# p1_control_block.net
KiCad netlist of a schematic drawn in Altium Designer
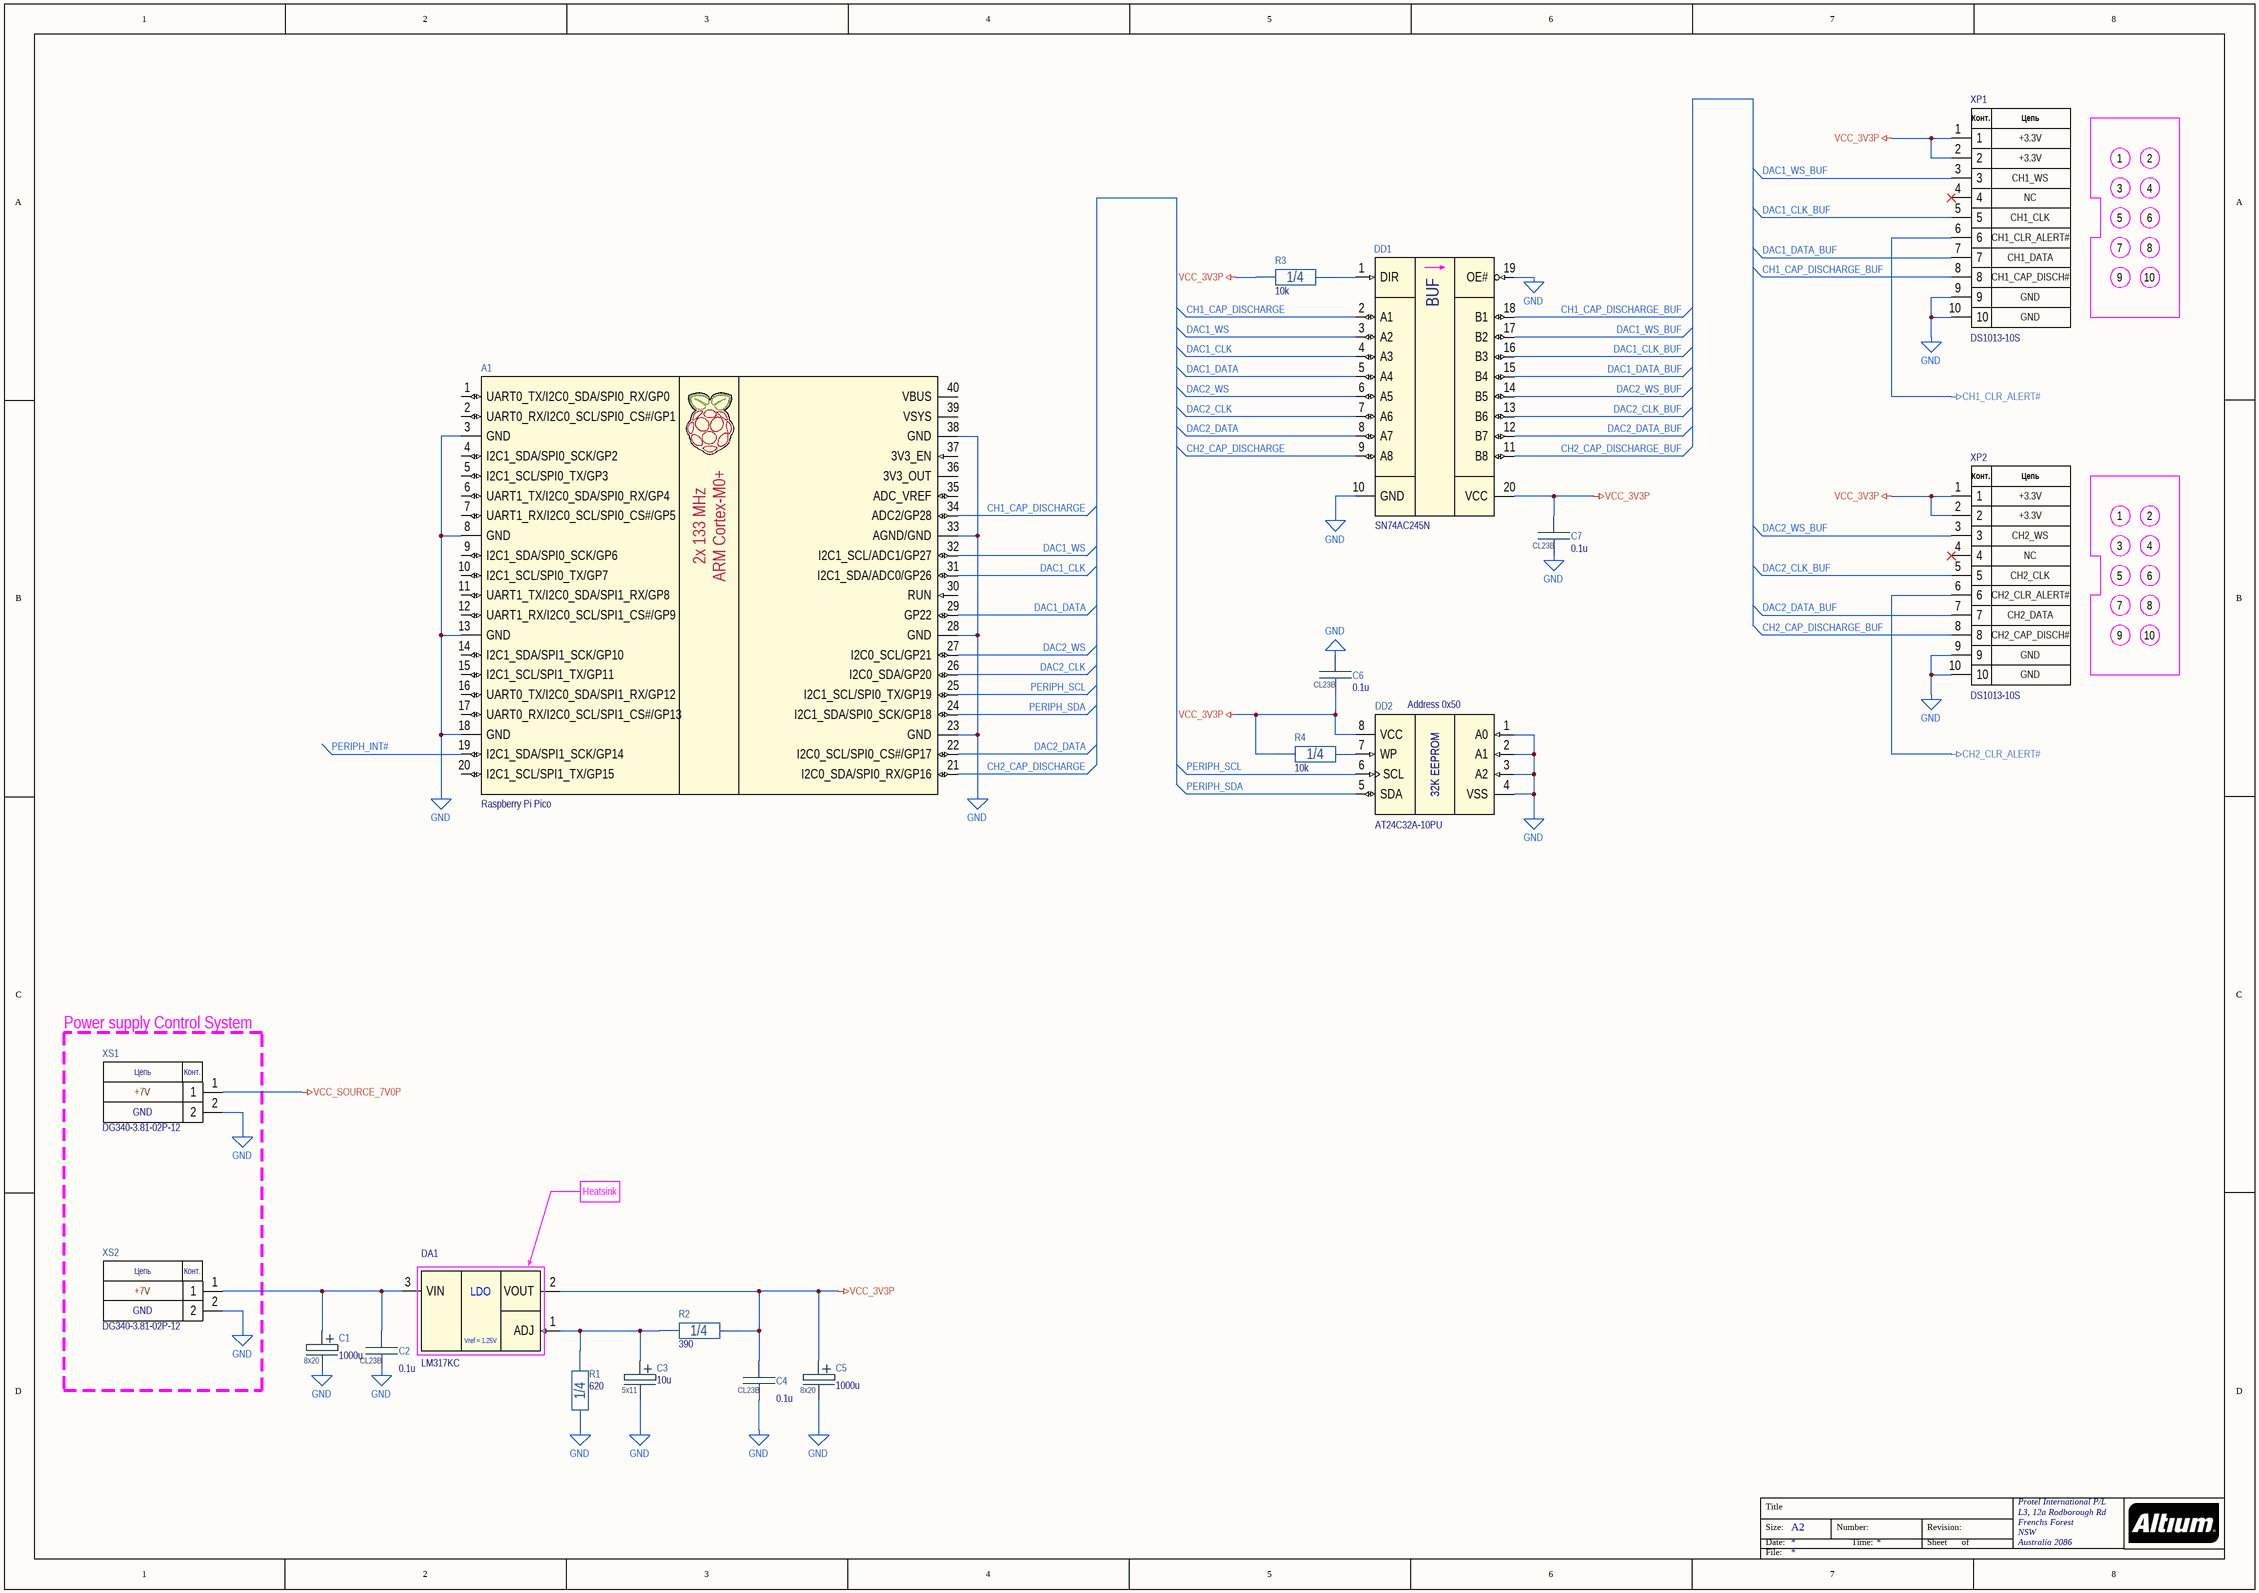
[diagram p0: p1_control_block.SchDoc]

(export (version "E")
  (design (tool "Eeschema 10.0.6"))
  (components
    (comp (ref "A1")
      (value "Raspberry Pi Pico")
      (footprint "PcbLib_Others:Raspberry_Pi_Pico")
      (description "Board Raspberry Pi Pico")
      (fields (field (name "MANUFACTURER") "Raspberry Pi"))
      (libsource (lib "Schlib_RaspberryPi") (part "Raspberry Pi Pico"))
    )
    (comp (ref "C1")
      (value "1000u")
      (footprint "PcbLib_RC:ECAP8X20X3.5_BRW")
      (description "Aluminium capacitor")
      (fields
        (field (name "TOLERANCE") "± 20 %")
        (field (name "VOLTAGE") "16V")
        (field (name "PACKAGE") "8x20")
      )
      (libsource (lib "Schlib_RC") (part "C_ECAP"))
    )
    (comp (ref "C2")
      (value "0.1u")
      (footprint "PcbLib_RC:CL23B_7.2x2.5")
      (description "Box-type metallized polyester film capacitor")
      (fields
        (field (name "TOLERANCE") "± * %")
        (field (name "VOLTAGE") "63V")
        (field (name "PACKAGE") "CL23B")
      )
      (libsource (lib "Schlib_RC") (part "CL23B"))
    )
    (comp (ref "C3")
      (value "10u")
      (footprint "PcbLib_RC:ECAP5X11X2.0_BRW")
      (description "Aluminium capacitor")
      (fields
        (field (name "TOLERANCE") "± 20 %")
        (field (name "VOLTAGE") "63V")
        (field (name "PACKAGE") "5x11")
      )
      (libsource (lib "Schlib_RC") (part "C_ECAP"))
    )
    (comp (ref "C4")
      (value "0.1u")
      (footprint "PcbLib_RC:CL23B_7.2x2.5")
      (description "Box-type metallized polyester film capacitor")
      (fields
        (field (name "TOLERANCE") "± * %")
        (field (name "VOLTAGE") "63V")
        (field (name "PACKAGE") "CL23B")
      )
      (libsource (lib "Schlib_RC") (part "CL23B"))
    )
    (comp (ref "C5")
      (value "1000u")
      (footprint "PcbLib_RC:ECAP8X20X3.5_BRW")
      (description "Aluminium capacitor")
      (fields
        (field (name "TOLERANCE") "± 20 %")
        (field (name "VOLTAGE") "16V")
        (field (name "PACKAGE") "8x20")
      )
      (libsource (lib "Schlib_RC") (part "C_ECAP"))
    )
    (comp (ref "C6")
      (value "0.1u")
      (footprint "PcbLib_RC:CL23B_7.2x2.5")
      (description "Box-type metallized polyester film capacitor")
      (fields
        (field (name "TOLERANCE") "± * %")
        (field (name "VOLTAGE") "63V")
        (field (name "PACKAGE") "CL23B")
      )
      (libsource (lib "Schlib_RC") (part "CL23B"))
    )
    (comp (ref "C7")
      (value "0.1u")
      (footprint "PcbLib_RC:CL23B_7.2x2.5")
      (description "Box-type metallized polyester film capacitor")
      (fields
        (field (name "TOLERANCE") "± * %")
        (field (name "VOLTAGE") "63V")
        (field (name "PACKAGE") "CL23B")
      )
      (libsource (lib "Schlib_RC") (part "CL23B"))
    )
    (comp (ref "DA1")
      (value "LM317KC")
      (footprint "PcbLib_ICs:TO-220A-3")
      (description "1.5 A 3-Terminal Adjustable Regulator")
      (fields (field (name "MANUFACTURER") "Texas Instruments"))
      (libsource (lib "Schlib_Texas_Instruments") (part "LM317KC"))
    )
    (comp (ref "DD1")
      (value "SN74AC245N")
      (footprint "PcbLib_ICs:DIP-20P-M01")
      (description "8-bit Bus Transceiver with 3-state outputs")
      (fields (field (name "MANUFACTURER") "Texas Instruments"))
      (libsource (lib "Schlib_Texas_Instruments") (part "SN74AC245N"))
    )
    (comp (ref "DD2")
      (value "AT24C32A-10PU")
      (footprint "PcbLib_ICs:DIP-8P-M01_with_SO8")
      (description "32K I2C Serial EEPROM")
      (fields (field (name "MANUFACTURER") "Microchip Technology"))
      (libsource (lib "Schlib_Microchip") (part "AT24C32A-10PU"))
    )
    (comp (ref "R1")
      (value "620")
      (footprint "PcbLib_RC:CFR-25")
      (description "Resistor 1/4W")
      (fields
        (field (name "TOLERANCE") "± 1 %")
        (field (name "PART NUMBER") "MFR-25FTF52-620R")
        (field (name "PACKAGE") "1/4")
      )
      (libsource (lib "Schlib_RC") (part "CF25"))
    )
    (comp (ref "R2")
      (value "390")
      (footprint "PcbLib_RC:CFR-25")
      (description "Resistor 1/4W")
      (fields
        (field (name "TOLERANCE") "± 1 %")
        (field (name "PART NUMBER") "MFR-25FTF52-390R")
        (field (name "PACKAGE") "1/4")
      )
      (libsource (lib "Schlib_RC") (part "CF25"))
    )
    (comp (ref "R3")
      (value "10k")
      (footprint "PcbLib_RC:CFR-25")
      (description "Resistor 1/4W")
      (fields
        (field (name "TOLERANCE") "± 1 %")
        (field (name "PART NUMBER") "MFR-25FTF52-10K")
        (field (name "PACKAGE") "1/4")
      )
      (libsource (lib "Schlib_RC") (part "CF25"))
    )
    (comp (ref "R4")
      (value "10k")
      (footprint "PcbLib_RC:CFR-25")
      (description "Resistor 1/4W")
      (fields
        (field (name "TOLERANCE") "± 1 %")
        (field (name "PART NUMBER") "MFR-25FTF52-10K")
        (field (name "PACKAGE") "1/4")
      )
      (libsource (lib "Schlib_RC") (part "CF25"))
    )
    (comp (ref "XP1")
      (value "DS1013-10S")
      (footprint "PcbLib_Pin_Headers_part2:BH-10")
      (description "10-pin 2.54 mm Box header elevator type")
      (fields (field (name "MANUFACTURER") "Connfly"))
      (libsource (lib "Schlib_Connfly") (part "BH-10"))
    )
    (comp (ref "XP2")
      (value "DS1013-10S")
      (footprint "PcbLib_Pin_Headers_part2:BH-10")
      (description "10-pin 2.54 mm Box header elevator type")
      (fields (field (name "MANUFACTURER") "Connfly"))
      (libsource (lib "Schlib_Connfly") (part "BH-10"))
    )
    (comp (ref "XS1")
      (value "DG340-3.81-02P-12")
      (footprint "PcbLib_Connectors:DG340-3.81-02P")
      (description "2-way screw terminal, pitch 150mils (3.81mm)")
      (fields (field (name "MANUFACTURER") "DEGSON"))
      (libsource (lib "Schlib_OtherComponents") (part "DG340-3.81-02P-12"))
    )
    (comp (ref "XS2")
      (value "DG340-3.81-02P-12")
      (footprint "PcbLib_Connectors:DG340-3.81-02P")
      (description "2-way screw terminal, pitch 150mils (3.81mm)")
      (fields (field (name "MANUFACTURER") "DEGSON"))
      (libsource (lib "Schlib_OtherComponents") (part "DG340-3.81-02P-12"))
    )
  )
  (nets
    (net (code "1") (name "/CH1_CAP_DISCHARGE") (class "Default")
      (node (ref "A1") (pin "34") (pinfunction "ADC2/GP28_34") (pintype "bidirectional"))
      (node (ref "DD1") (pin "2") (pinfunction "A1_2") (pintype "bidirectional"))
    )
    (net (code "2") (name "/CH1_CAP_DISCHARGE_BUF") (class "Default")
      (node (ref "DD1") (pin "18") (pinfunction "B1_18") (pintype "bidirectional"))
      (node (ref "XP1") (pin "8") (pinfunction "8_8") (pintype "passive"))
    )
    (net (code "3") (name "/CH2_CAP_DISCHARGE") (class "Default")
      (node (ref "A1") (pin "21") (pinfunction "I2C0_SDA/SPI0_RX/GP16_21") (pintype "bidirectional"))
      (node (ref "DD1") (pin "9") (pinfunction "A8_9") (pintype "bidirectional"))
    )
    (net (code "4") (name "/CH2_CAP_DISCHARGE_BUF") (class "Default")
      (node (ref "DD1") (pin "11") (pinfunction "B8_11") (pintype "bidirectional"))
      (node (ref "XP2") (pin "8") (pinfunction "8_8") (pintype "passive"))
    )
    (net (code "5") (name "/DAC1_CLK") (class "Default")
      (node (ref "A1") (pin "31") (pinfunction "I2C1_SDA/ADC0/GP26_31") (pintype "bidirectional"))
      (node (ref "DD1") (pin "4") (pinfunction "A3_4") (pintype "bidirectional"))
    )
    (net (code "6") (name "/DAC1_CLK_BUF") (class "Default")
      (node (ref "DD1") (pin "16") (pinfunction "B3_16") (pintype "bidirectional"))
      (node (ref "XP1") (pin "5") (pinfunction "5_5") (pintype "passive"))
    )
    (net (code "7") (name "/DAC1_DATA") (class "Default")
      (node (ref "A1") (pin "29") (pinfunction "GP22_29") (pintype "bidirectional"))
      (node (ref "DD1") (pin "5") (pinfunction "A4_5") (pintype "bidirectional"))
    )
    (net (code "8") (name "/DAC1_DATA_BUF") (class "Default")
      (node (ref "DD1") (pin "15") (pinfunction "B4_15") (pintype "bidirectional"))
      (node (ref "XP1") (pin "7") (pinfunction "7_7") (pintype "passive"))
    )
    (net (code "9") (name "/DAC1_WS") (class "Default")
      (node (ref "A1") (pin "32") (pinfunction "I2C1_SCL/ADC1/GP27_32") (pintype "bidirectional"))
      (node (ref "DD1") (pin "3") (pinfunction "A2_3") (pintype "bidirectional"))
    )
    (net (code "10") (name "/DAC1_WS_BUF") (class "Default")
      (node (ref "DD1") (pin "17") (pinfunction "B2_17") (pintype "bidirectional"))
      (node (ref "XP1") (pin "3") (pinfunction "3_3") (pintype "passive"))
    )
    (net (code "11") (name "/DAC2_CLK") (class "Default")
      (node (ref "A1") (pin "26") (pinfunction "I2C0_SDA/GP20_26") (pintype "bidirectional"))
      (node (ref "DD1") (pin "7") (pinfunction "A6_7") (pintype "bidirectional"))
    )
    (net (code "12") (name "/DAC2_CLK_BUF") (class "Default")
      (node (ref "DD1") (pin "13") (pinfunction "B6_13") (pintype "bidirectional"))
      (node (ref "XP2") (pin "5") (pinfunction "5_5") (pintype "passive"))
    )
    (net (code "13") (name "/DAC2_DATA") (class "Default")
      (node (ref "A1") (pin "22") (pinfunction "I2C0_SCL/SPI0_CS#/GP17_22") (pintype "bidirectional"))
      (node (ref "DD1") (pin "8") (pinfunction "A7_8") (pintype "bidirectional"))
    )
    (net (code "14") (name "/DAC2_DATA_BUF") (class "Default")
      (node (ref "DD1") (pin "12") (pinfunction "B7_12") (pintype "bidirectional"))
      (node (ref "XP2") (pin "7") (pinfunction "7_7") (pintype "passive"))
    )
    (net (code "15") (name "/DAC2_WS") (class "Default")
      (node (ref "A1") (pin "27") (pinfunction "I2C0_SCL/GP21_27") (pintype "bidirectional"))
      (node (ref "DD1") (pin "6") (pinfunction "A5_6") (pintype "bidirectional"))
    )
    (net (code "16") (name "/DAC2_WS_BUF") (class "Default")
      (node (ref "DD1") (pin "14") (pinfunction "B5_14") (pintype "bidirectional"))
      (node (ref "XP2") (pin "3") (pinfunction "3_3") (pintype "passive"))
    )
    (net (code "17") (name "/PERIPH_INT#") (class "Default")
      (node (ref "A1") (pin "19") (pinfunction "I2C1_SDA/SPI1_SCK/GP14_19") (pintype "bidirectional"))
    )
    (net (code "18") (name "/PERIPH_SCL") (class "Default")
      (node (ref "A1") (pin "25") (pinfunction "I2C1_SCL/SPI0_TX/GP19_25") (pintype "bidirectional"))
      (node (ref "DD2") (pin "6") (pinfunction "SCL_6") (pintype "input"))
    )
    (net (code "19") (name "/PERIPH_SDA") (class "Default")
      (node (ref "A1") (pin "24") (pinfunction "I2C1_SDA/SPI0_SCK/GP18_24") (pintype "bidirectional"))
      (node (ref "DD2") (pin "5") (pinfunction "SDA_5") (pintype "bidirectional"))
    )
    (net (code "20") (name "CH1_CLR_ALERT#") (class "Default")
      (node (ref "XP1") (pin "6") (pinfunction "6_6") (pintype "passive"))
    )
    (net (code "21") (name "CH2_CLR_ALERT#") (class "Default")
      (node (ref "XP2") (pin "6") (pinfunction "6_6") (pintype "passive"))
    )
    (net (code "22") (name "GND") (class "Default")
      (node (ref "A1") (pin "13") (pinfunction "GND_13") (pintype "power_in"))
      (node (ref "A1") (pin "18") (pinfunction "GND_18") (pintype "power_in"))
      (node (ref "A1") (pin "23") (pinfunction "GND_23") (pintype "power_in"))
      (node (ref "A1") (pin "28") (pinfunction "GND_28") (pintype "power_in"))
      (node (ref "A1") (pin "3") (pinfunction "GND_3") (pintype "power_in"))
      (node (ref "A1") (pin "33") (pinfunction "AGND/GND_33") (pintype "power_in"))
      (node (ref "A1") (pin "38") (pinfunction "GND_38") (pintype "power_in"))
      (node (ref "A1") (pin "8") (pinfunction "GND_8") (pintype "power_in"))
      (node (ref "C1") (pin "2") (pinfunction "2_2") (pintype "passive"))
      (node (ref "C2") (pin "2") (pinfunction "2_2") (pintype "passive"))
      (node (ref "C3") (pin "2") (pinfunction "2_2") (pintype "passive"))
      (node (ref "C4") (pin "2") (pinfunction "2_2") (pintype "passive"))
      (node (ref "C5") (pin "2") (pinfunction "2_2") (pintype "passive"))
      (node (ref "C6") (pin "1") (pinfunction "1_1") (pintype "passive"))
      (node (ref "C7") (pin "2") (pinfunction "2_2") (pintype "passive"))
      (node (ref "DD1") (pin "10") (pinfunction "GND_10") (pintype "power_in"))
      (node (ref "DD1") (pin "19") (pinfunction "OE#_19") (pintype "input"))
      (node (ref "DD2") (pin "1") (pinfunction "A0_1") (pintype "input"))
      (node (ref "DD2") (pin "2") (pinfunction "A1_2") (pintype "input"))
      (node (ref "DD2") (pin "3") (pinfunction "A2_3") (pintype "input"))
      (node (ref "DD2") (pin "4") (pinfunction "VSS_4") (pintype "power_in"))
      (node (ref "R1") (pin "1") (pinfunction "1_1") (pintype "passive"))
      (node (ref "XP1") (pin "10") (pinfunction "10_10") (pintype "passive"))
      (node (ref "XP1") (pin "9") (pinfunction "9_9") (pintype "passive"))
      (node (ref "XP2") (pin "10") (pinfunction "10_10") (pintype "passive"))
      (node (ref "XP2") (pin "9") (pinfunction "9_9") (pintype "passive"))
      (node (ref "XS1") (pin "2") (pinfunction "2_2") (pintype "passive"))
      (node (ref "XS2") (pin "2") (pinfunction "2_2") (pintype "passive"))
    )
    (net (code "23") (name "Net-(DA1-ADJ)") (class "Default")
      (node (ref "C3") (pin "1") (pinfunction "1_1") (pintype "passive"))
      (node (ref "DA1") (pin "1") (pinfunction "ADJ_1") (pintype "input"))
      (node (ref "R1") (pin "2") (pinfunction "2_2") (pintype "passive"))
      (node (ref "R2") (pin "2") (pinfunction "2_2") (pintype "passive"))
    )
    (net (code "24") (name "Net-(DA1-VIN)") (class "Default")
      (node (ref "C1") (pin "1") (pinfunction "1_1") (pintype "passive"))
      (node (ref "C2") (pin "1") (pinfunction "1_1") (pintype "passive"))
      (node (ref "DA1") (pin "3") (pinfunction "VIN_3") (pintype "power_in"))
      (node (ref "XS2") (pin "1") (pinfunction "1_1") (pintype "passive"))
    )
    (net (code "25") (name "Net-(DD1-DIR)") (class "Default")
      (node (ref "DD1") (pin "1") (pinfunction "DIR_1") (pintype "input"))
      (node (ref "R3") (pin "2") (pinfunction "2_2") (pintype "passive"))
    )
    (net (code "26") (name "Net-(DD2-WP)") (class "Default")
      (node (ref "DD2") (pin "7") (pinfunction "WP_7") (pintype "input"))
      (node (ref "R4") (pin "2") (pinfunction "2_2") (pintype "passive"))
    )
    (net (code "27") (name "VCC_3V3P") (class "Default")
      (node (ref "C4") (pin "1") (pinfunction "1_1") (pintype "passive"))
      (node (ref "C5") (pin "1") (pinfunction "1_1") (pintype "passive"))
      (node (ref "C6") (pin "2") (pinfunction "2_2") (pintype "passive"))
      (node (ref "C7") (pin "1") (pinfunction "1_1") (pintype "passive"))
      (node (ref "DA1") (pin "2") (pinfunction "VOUT_2") (pintype "power_in"))
      (node (ref "DD1") (pin "20") (pinfunction "VCC_20") (pintype "power_in"))
      (node (ref "DD2") (pin "8") (pinfunction "VCC_8") (pintype "power_in"))
      (node (ref "R2") (pin "1") (pinfunction "1_1") (pintype "passive"))
      (node (ref "R3") (pin "1") (pinfunction "1_1") (pintype "passive"))
      (node (ref "R4") (pin "1") (pinfunction "1_1") (pintype "passive"))
      (node (ref "XP1") (pin "1") (pinfunction "1_1") (pintype "passive"))
      (node (ref "XP1") (pin "2") (pinfunction "2_2") (pintype "passive"))
      (node (ref "XP2") (pin "1") (pinfunction "1_1") (pintype "passive"))
      (node (ref "XP2") (pin "2") (pinfunction "2_2") (pintype "passive"))
    )
    (net (code "28") (name "VCC_SOURCE_7V0P") (class "Default")
      (node (ref "XS1") (pin "1") (pinfunction "1_1") (pintype "passive"))
    )
    (net (code "29") (name "unconnected-(A1-3V3_EN-Pad37)") (class "Default")
      (node (ref "A1") (pin "37") (pinfunction "3V3_EN_37") (pintype "input"))
    )
    (net (code "30") (name "unconnected-(A1-3V3_OUT-Pad36)") (class "Default")
      (node (ref "A1") (pin "36") (pinfunction "3V3_OUT_36") (pintype "power_in"))
    )
    (net (code "31") (name "unconnected-(A1-ADC_VREF-Pad35)") (class "Default")
      (node (ref "A1") (pin "35") (pinfunction "ADC_VREF_35") (pintype "bidirectional"))
    )
    (net (code "32") (name "unconnected-(A1-I2C1_SCL{slash}SPI0_TX{slash}GP3-Pad5)") (class "Default")
      (node (ref "A1") (pin "5") (pinfunction "I2C1_SCL/SPI0_TX/GP3_5") (pintype "bidirectional"))
    )
    (net (code "33") (name "unconnected-(A1-I2C1_SCL{slash}SPI0_TX{slash}GP7-Pad10)") (class "Default")
      (node (ref "A1") (pin "10") (pinfunction "I2C1_SCL/SPI0_TX/GP7_10") (pintype "bidirectional"))
    )
    (net (code "34") (name "unconnected-(A1-I2C1_SCL{slash}SPI1_TX{slash}GP11-Pad15)") (class "Default")
      (node (ref "A1") (pin "15") (pinfunction "I2C1_SCL/SPI1_TX/GP11_15") (pintype "bidirectional"))
    )
    (net (code "35") (name "unconnected-(A1-I2C1_SCL{slash}SPI1_TX{slash}GP15-Pad20)") (class "Default")
      (node (ref "A1") (pin "20") (pinfunction "I2C1_SCL/SPI1_TX/GP15_20") (pintype "bidirectional"))
    )
    (net (code "36") (name "unconnected-(A1-I2C1_SDA{slash}SPI0_SCK{slash}GP2-Pad4)") (class "Default")
      (node (ref "A1") (pin "4") (pinfunction "I2C1_SDA/SPI0_SCK/GP2_4") (pintype "bidirectional"))
    )
    (net (code "37") (name "unconnected-(A1-I2C1_SDA{slash}SPI0_SCK{slash}GP6-Pad9)") (class "Default")
      (node (ref "A1") (pin "9") (pinfunction "I2C1_SDA/SPI0_SCK/GP6_9") (pintype "bidirectional"))
    )
    (net (code "38") (name "unconnected-(A1-I2C1_SDA{slash}SPI1_SCK{slash}GP10-Pad14)") (class "Default")
      (node (ref "A1") (pin "14") (pinfunction "I2C1_SDA/SPI1_SCK/GP10_14") (pintype "bidirectional"))
    )
    (net (code "39") (name "unconnected-(A1-RUN-Pad30)") (class "Default")
      (node (ref "A1") (pin "30") (pinfunction "RUN_30") (pintype "input"))
    )
    (net (code "40") (name "unconnected-(A1-UART0_RX{slash}I2C0_SCL{slash}SPI0_CS#{slash}GP1-Pad2)") (class "Default")
      (node (ref "A1") (pin "2") (pinfunction "UART0_RX/I2C0_SCL/SPI0_CS#/GP1_2") (pintype "bidirectional"))
    )
    (net (code "41") (name "unconnected-(A1-UART0_RX{slash}I2C0_SCL{slash}SPI1_CS#{slash}GP13-Pad17)") (class "Default")
      (node (ref "A1") (pin "17") (pinfunction "UART0_RX/I2C0_SCL/SPI1_CS#/GP13_17") (pintype "bidirectional"))
    )
    (net (code "42") (name "unconnected-(A1-UART0_TX{slash}I2C0_SDA{slash}SPI0_RX{slash}GP0-Pad1)") (class "Default")
      (node (ref "A1") (pin "1") (pinfunction "UART0_TX/I2C0_SDA/SPI0_RX/GP0_1") (pintype "bidirectional"))
    )
    (net (code "43") (name "unconnected-(A1-UART0_TX{slash}I2C0_SDA{slash}SPI1_RX{slash}GP12-Pad16)") (class "Default")
      (node (ref "A1") (pin "16") (pinfunction "UART0_TX/I2C0_SDA/SPI1_RX/GP12_16") (pintype "bidirectional"))
    )
    (net (code "44") (name "unconnected-(A1-UART1_RX{slash}I2C0_SCL{slash}SPI0_CS#{slash}GP5-Pad7)") (class "Default")
      (node (ref "A1") (pin "7") (pinfunction "UART1_RX/I2C0_SCL/SPI0_CS#/GP5_7") (pintype "bidirectional"))
    )
    (net (code "45") (name "unconnected-(A1-UART1_RX{slash}I2C0_SCL{slash}SPI1_CS#{slash}GP9-Pad12)") (class "Default")
      (node (ref "A1") (pin "12") (pinfunction "UART1_RX/I2C0_SCL/SPI1_CS#/GP9_12") (pintype "bidirectional"))
    )
    (net (code "46") (name "unconnected-(A1-UART1_TX{slash}I2C0_SDA{slash}SPI0_RX{slash}GP4-Pad6)") (class "Default")
      (node (ref "A1") (pin "6") (pinfunction "UART1_TX/I2C0_SDA/SPI0_RX/GP4_6") (pintype "bidirectional"))
    )
    (net (code "47") (name "unconnected-(A1-UART1_TX{slash}I2C0_SDA{slash}SPI1_RX{slash}GP8-Pad11)") (class "Default")
      (node (ref "A1") (pin "11") (pinfunction "UART1_TX/I2C0_SDA/SPI1_RX/GP8_11") (pintype "bidirectional"))
    )
    (net (code "48") (name "unconnected-(A1-VBUS-Pad40)") (class "Default")
      (node (ref "A1") (pin "40") (pinfunction "VBUS_40") (pintype "power_in"))
    )
    (net (code "49") (name "unconnected-(A1-VSYS-Pad39)") (class "Default")
      (node (ref "A1") (pin "39") (pinfunction "VSYS_39") (pintype "power_in"))
    )
    (net (code "50") (name "unconnected-(XP1-Pad4)") (class "Default")
      (node (ref "XP1") (pin "4") (pinfunction "4_4") (pintype "passive+no_connect"))
    )
    (net (code "51") (name "unconnected-(XP2-Pad4)") (class "Default")
      (node (ref "XP2") (pin "4") (pinfunction "4_4") (pintype "passive+no_connect"))
    )
  )
)
